# RedBoard.net
KiCad netlist of a schematic drawn in Altium Designer
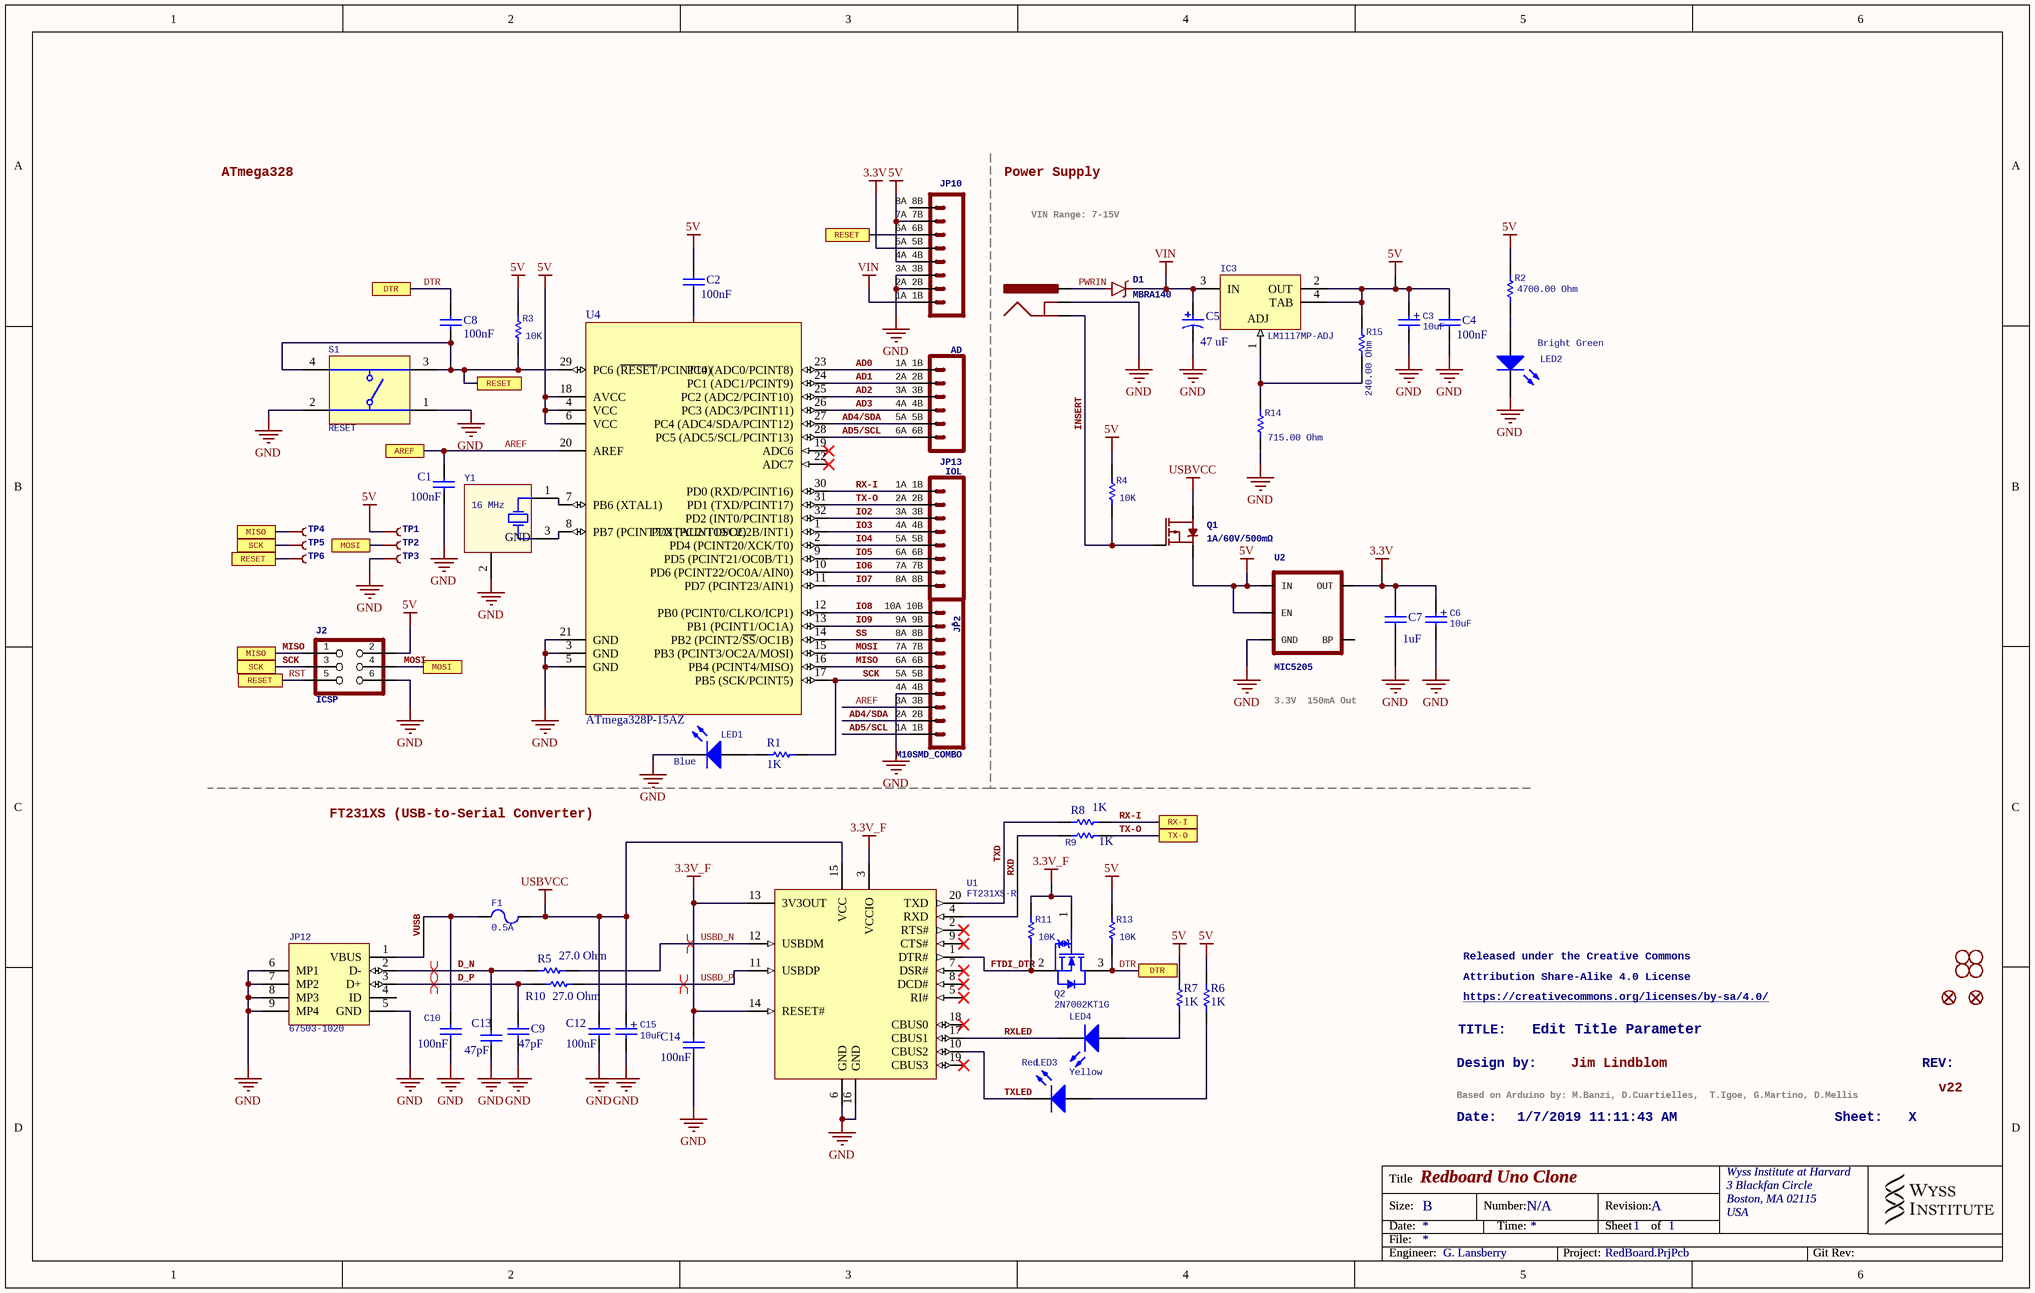
[diagram p0: RedBoard.SchDoc]

(export (version "E")
  (design (tool "Eeschema 10.0.6"))
  (components
    (comp (ref "C1")
      (value "100nF")
      (footprint "CAPC0402(1005)60_M")
      (description "CAP 100nF 10V -20% to +80% 0402 (1005 Metric) Thickness 0.6mm SMD")
      (fields (field (name "TOLERANCE") "-20% to +80%") (field (name "Comment") "CAP 100nF 10V 0402(1005)"))
      (libsource (lib "Altium Content Vault") (part "CAP"))
    )
    (comp (ref "C2")
      (value "100nF")
      (footprint "CAPC0402(1005)60_M")
      (description "CAP 100nF 10V -20% to +80% 0402 (1005 Metric) Thickness 0.6mm SMD")
      (fields (field (name "TOLERANCE") "-20% to +80%") (field (name "Comment") "CAP 100nF 10V 0402(1005)"))
      (libsource (lib "Altium Content Vault") (part "CAP"))
    )
    (comp (ref "C3")
      (value "10uF")
      (footprint "CAP_0603_TANT:CAPC2113X120X50NL20T30X")
      (fields
        (field (name "MANUFACTURER") "AVX Interconnect / Elco")
        (field (name "PART NUMBER") "TAJP106M010RNJ")
      )
      (libsource (lib "CAP_0603_TANT") (part "CAP_0603_TANT"))
    )
    (comp (ref "C4")
      (value "100nF")
      (footprint "CAPC0402(1005)60_M")
      (description "CAP 100nF 10V -20% to +80% 0402 (1005 Metric) Thickness 0.6mm SMD")
      (fields (field (name "TOLERANCE") "-20% to +80%") (field (name "Comment") "CAP 100nF 10V 0402(1005)"))
      (libsource (lib "Altium Content Vault") (part "CAP"))
    )
    (comp (ref "C5")
      (value "EEE-FT1E470AR")
      (footprint "PNSC-FT-V-53x53-2_V")
      (fields (field (name "CAP.") "47 uF") (field (name "MANUFACTURER") "Panasonic"))
      (libsource (lib "Altium Content Vault") (part "PNSC-CAP-P-2"))
    )
    (comp (ref "C6")
      (value "10uF")
      (footprint "CAP_0603_TANT:CAPC2113X120X50NL20T30X")
      (fields
        (field (name "MANUFACTURER") "AVX Interconnect / Elco")
        (field (name "PART NUMBER") "TAJP106M010RNJ")
      )
      (libsource (lib "CAP_0603_TANT") (part "CAP_0603_TANT"))
    )
    (comp (ref "C7")
      (value "1uF")
      (footprint "CAPC0402(1005)60_N")
      (description "CAP 1uF 10V -20% to +80% 0402 (1005 Metric) Thickness 0.6mm SMD")
      (fields (field (name "TOLERANCE") "-20% to +80%") (field (name "Comment") "CAP 1uF 10V 0402(1005)"))
      (libsource (lib "Altium Content Vault") (part "CAP"))
    )
    (comp (ref "C8")
      (value "100nF")
      (footprint "CAPC0402(1005)60_M")
      (description "CAP 100nF 10V -20% to +80% 0402 (1005 Metric) Thickness 0.6mm SMD")
      (fields (field (name "TOLERANCE") "-20% to +80%") (field (name "Comment") "CAP 100nF 10V 0402(1005)"))
      (libsource (lib "Altium Content Vault") (part "CAP"))
    )
    (comp (ref "C9")
      (value "47pF")
      (footprint "CAPC0402(1005)60_M")
      (description "CAP 47pF 10V ±1% 0402 (1005 Metric) Thickness 0.6mm SMD")
      (fields (field (name "TOLERANCE") "Â±1%") (field (name "Comment") "CAP 47pF 10V 0402(1005)"))
      (libsource (lib "Altium Content Vault") (part "CAP"))
    )
    (comp (ref "C10")
      (value "100nF")
      (footprint "CAPC0402(1005)60_M")
      (description "CAP 100nF 10V -20% to +80% 0402 (1005 Metric) Thickness 0.6mm SMD")
      (fields (field (name "TOLERANCE") "-20% to +80%") (field (name "Comment") "CAP 100nF 10V 0402(1005)"))
      (libsource (lib "Altium Content Vault") (part "CAP"))
    )
    (comp (ref "C12")
      (value "100nF")
      (footprint "CAPC0402(1005)60_M")
      (description "CAP 100nF 10V -20% to +80% 0402 (1005 Metric) Thickness 0.6mm SMD")
      (fields (field (name "TOLERANCE") "-20% to +80%") (field (name "Comment") "CAP 100nF 10V 0402(1005)"))
      (libsource (lib "Altium Content Vault") (part "CAP"))
    )
    (comp (ref "C13")
      (value "47pF")
      (footprint "CAPC0402(1005)60_M")
      (description "CAP 47pF 10V ±1% 0402 (1005 Metric) Thickness 0.6mm SMD")
      (fields (field (name "TOLERANCE") "Â±1%") (field (name "Comment") "CAP 47pF 10V 0402(1005)"))
      (libsource (lib "Altium Content Vault") (part "CAP"))
    )
    (comp (ref "C14")
      (value "100nF")
      (footprint "CAPC0402(1005)60_M")
      (description "CAP 100nF 10V -20% to +80% 0402 (1005 Metric) Thickness 0.6mm SMD")
      (fields (field (name "TOLERANCE") "-20% to +80%") (field (name "Comment") "CAP 100nF 10V 0402(1005)"))
      (libsource (lib "Altium Content Vault") (part "CAP"))
    )
    (comp (ref "C15")
      (value "10uF")
      (footprint "CAP_0603_TANT:CAPC2113X120X50NL20T30X")
      (fields
        (field (name "MANUFACTURER") "AVX Interconnect / Elco")
        (field (name "PART NUMBER") "TAJP106M010RNJ")
      )
      (libsource (lib "CAP_0603_TANT") (part "CAP_0603_TANT"))
    )
    (comp (ref "D1")
      (value "MBRA140")
      (footprint "ONSC-SMA-2-403D-02_V")
      (description "40V, 1A Schottky rectifierSMA/DO-214AC packageDIO-08053")
      (fields
        (field (name "MANUFACTURER") "ON Semiconductor")
        (field (name "MANUFACTURER PART NUMBER") "MBRA140T3G")
      )
      (libsource (lib "SparkFun-DiscreteSemi") (part "MBRA140"))
    )
    (comp (ref "F1")
      (value "0.5A")
      (footprint "LFUS-1812L050_V")
      (fields (field (name "TOLERANCE") "1%"))
      (libsource (lib "Altium Content Vault") (part "FUSE-2"))
    )
    (comp (ref "IC3")
      (value "LM1117MP-ADJ")
      (footprint "DCY0004A_L")
      (description "800mA Low-Dropout Linear Regulator, 4-pin SOT-223, Pb-Free")
      (fields
        (field (name "PARTNUMBER") "LM1117MP-ADJ/NOPB")
        (field (name "MANUFACTURER") "Texas Instruments")
      )
      (libsource (lib "Altium Content Vault") (part "PM-REG-LM1086ADJ-SOT4"))
    )
    (comp (ref "J2")
      (value "ICSP")
      (footprint "2X3_SMT_POSTS")
      (libsource (lib "SparkFun-Connectors") (part "AVR_SPI_PROG_3X2SMD"))
    )
    (comp (ref "J3")
      (value "POWER_JACKSUPER_BOMB_DIGITY")
      (footprint "POWER_JACK_SMD_OVERPASTE_SUPER_BOMB_DIGITY")
      (fields (field (name "LIBRARYNAME") "Testing"))
      (libsource (lib "Testing") (part "POWER_JACKSUPER_BOMB_DIGITY"))
    )
    (comp (ref "JP2")
      (value "M10SMD_COMBO")
      (footprint "1X10_SMD_COMBINED")
      (fields (field (name "NAME") "*"))
      (libsource (lib "SparkFun-Connectors") (part "M10SMD_COMBO"))
    )
    (comp (ref "JP3")
      (value "STAND-OFF")
      (footprint "STAND-OFF")
      (libsource (lib "SparkFun") (part "STAND-OFF"))
    )
    (comp (ref "JP4")
      (value "STAND-OFF")
      (footprint "STAND-OFF")
      (libsource (lib "SparkFun") (part "STAND-OFF"))
    )
    (comp (ref "JP5")
      (value "STAND-OFF")
      (footprint "STAND-OFF")
      (libsource (lib "SparkFun") (part "STAND-OFF"))
    )
    (comp (ref "JP6")
      (value "STAND-OFF")
      (footprint "STAND-OFF")
      (libsource (lib "SparkFun") (part "STAND-OFF"))
    )
    (comp (ref "JP8")
      (value "FIDUCIAL1X2")
      (footprint "FID")
      (description "Fiducial Alignment PointsVarious fiducial points for machine vision alignment.")
      (libsource (lib "SparkFun") (part "FIDUCIAL1X2"))
    )
    (comp (ref "JP9")
      (value "FIDUCIAL1X2")
      (footprint "FID")
      (description "Fiducial Alignment PointsVarious fiducial points for machine vision alignment.")
      (libsource (lib "SparkFun") (part "FIDUCIAL1X2"))
    )
    (comp (ref "JP10")
      (value "M08SMD-COMBO")
      (footprint "1X08_SMD_COMBINED")
      (libsource (lib "SparkFun-Connectors") (part "M08SMD-COMBO"))
    )
    (comp (ref "JP11")
      (value "IOL")
      (footprint "1X08_SMD_COMBINED")
      (libsource (lib "SparkFun-Connectors") (part "M08SMD-COMBO"))
    )
    (comp (ref "JP12")
      (value "67503-1020")
      (footprint "MOLX-67503-1020_V")
      (description "USB, MINI, SMD, RA KME04-USBMU03A01")
      (fields (field (name "MANUFACTURER") "Molex"))
      (libsource (lib "Altium Content Vault") (part "MOLX-67503-1020"))
    )
    (comp (ref "JP13")
      (value "AD")
      (footprint "1X06_SMD_STRAIGHT_COMBO")
      (libsource (lib "SparkFun-Connectors") (part "M06SMD-STRAIGHT-COMBO"))
    )
    (comp (ref "LED1")
      (value "150060BS75000")
      (footprint "0603_A")
      (description "SMD mono-color Chip LED, WL-SMCW, Blue")
      (fields (field (name "COLOR") "Blue") (field (name "MANUFACTURER") "Wuerth Elektronik"))
      (libsource (lib "Altium Content Vault") (part "WE-LED_K1A2-2"))
    )
    (comp (ref "LED2")
      (value "150060VS75000")
      (footprint "0603_A")
      (description "SMD mono-color Chip LED, WL-SMCW, Bright Green")
      (fields (field (name "COLOR") "Bright Green") (field (name "MANUFACTURER") "Wuerth Elektronik"))
      (libsource (lib "Altium Content Vault") (part "WE-LED_K1A2-2"))
    )
    (comp (ref "LED3")
      (value "150060RS75000")
      (footprint "0603_A")
      (description "SMD mono-color Chip LED, WL-SMCW, Red")
      (fields (field (name "COLOR") "Red") (field (name "MANUFACTURER") "Wuerth Elektronik"))
      (libsource (lib "Altium Content Vault") (part "WE-LED_K1A2-2"))
    )
    (comp (ref "LED4")
      (value "150060YS75000")
      (footprint "0603_A")
      (description "SMD mono-color Chip LED, WL-SMCW, Yellow")
      (fields (field (name "COLOR") "Yellow") (field (name "MANUFACTURER") "Wuerth Elektronik"))
      (libsource (lib "Altium Content Vault") (part "WE-LED_K1A2-2"))
    )
    (comp (ref "Q1")
      (value "1A/60V/500mΩ")
      (footprint "SOT23-3")
      (description "P-channel MOSFETsVoltage controlled devices that allow control of high current outputs.")
      (fields
        (field (name "MANUFACTURER") "Diodes Zetex")
        (field (name "MANUFACTURER PART NUMBER") "ZXMP6A13FTA")
      )
      (libsource (lib "SparkFun-DiscreteSemi") (part "MOSFET-PCH-ZXMP6A13F"))
    )
    (comp (ref "Q2")
      (value "2N7002KT1G")
      (footprint "ONSC-SOT-23-3-318-08_V")
      (description "Small Signal MOSFET, 60 V, 380 mA, Single, N-Channel, 3-Pin SOT-23, Pb-Free, Tape and Reel")
      (fields (field (name "MANUFACTURER") "On Semiconductor"))
      (libsource (lib "Altium Content Vault") (part "ONSC-NMOS-G1S2D3-3_B"))
    )
    (comp (ref "R1")
      (value "1K")
      (footprint "RESC0402(1005)_L")
      (description "1K 0.063W 1% 0402 (1005 Metric)  SMD")
      (fields (field (name "TOLERANCE") "1 %") (field (name "POWER") "0.063 W"))
      (libsource (lib "Altium Content Vault") (part "RES"))
    )
    (comp (ref "R2")
      (value "4700.00 Ohm")
      (footprint "RESC0402(1005)_N")
      (description "4K7 0.063W 1% 0402 (1005 Metric)  SMD")
      (fields (field (name "POWER") "0.063 W") (field (name "TOLERANCE") "1 %"))
      (libsource (lib "Altium Content Vault") (part "RES"))
    )
    (comp (ref "R3")
      (value "10K")
      (footprint "RESC0402(1005)_N")
      (description "10K 0.063W 1% 0402 (1005 Metric)  SMD")
      (fields (field (name "TOLERANCE") "1 %") (field (name "POWER") "0.063 W"))
      (libsource (lib "Altium Content Vault") (part "RES"))
    )
    (comp (ref "R4")
      (value "10K")
      (footprint "RESC0402(1005)_N")
      (description "10K 0.063W 1% 0402 (1005 Metric)  SMD")
      (fields (field (name "TOLERANCE") "1 %") (field (name "POWER") "0.063 W"))
      (libsource (lib "Altium Content Vault") (part "RES"))
    )
    (comp (ref "R5")
      (value "27.0 Ohm")
      (footprint "RESC0402(1005)_M")
      (description "27R 0.063W 1% 0402 (1005 Metric)  SMD")
      (fields (field (name "POWER") "0.063 W") (field (name "TOLERANCE") "1 %"))
      (libsource (lib "Altium Content Vault") (part "RES"))
    )
    (comp (ref "R6")
      (value "1K")
      (footprint "RESC0402(1005)_L")
      (description "1K 0.063W 1% 0402 (1005 Metric)  SMD")
      (fields (field (name "TOLERANCE") "1 %") (field (name "POWER") "0.063 W"))
      (libsource (lib "Altium Content Vault") (part "RES"))
    )
    (comp (ref "R7")
      (value "1K")
      (footprint "RESC0402(1005)_L")
      (description "1K 0.063W 1% 0402 (1005 Metric)  SMD")
      (fields (field (name "TOLERANCE") "1 %") (field (name "POWER") "0.063 W"))
      (libsource (lib "Altium Content Vault") (part "RES"))
    )
    (comp (ref "R8")
      (value "1K")
      (footprint "RESC0402(1005)_L")
      (description "1K 0.063W 1% 0402 (1005 Metric)  SMD")
      (fields (field (name "TOLERANCE") "1 %") (field (name "POWER") "0.063 W"))
      (libsource (lib "Altium Content Vault") (part "RES"))
    )
    (comp (ref "R9")
      (value "1K")
      (footprint "RESC0402(1005)_L")
      (description "1K 0.063W 1% 0402 (1005 Metric)  SMD")
      (fields (field (name "TOLERANCE") "1 %") (field (name "POWER") "0.063 W"))
      (libsource (lib "Altium Content Vault") (part "RES"))
    )
    (comp (ref "R10")
      (value "27.0 Ohm")
      (footprint "RESC0402(1005)_M")
      (description "27R 0.063W 1% 0402 (1005 Metric)  SMD")
      (fields (field (name "POWER") "0.063 W") (field (name "TOLERANCE") "1 %"))
      (libsource (lib "Altium Content Vault") (part "RES"))
    )
    (comp (ref "R11")
      (value "10K")
      (footprint "RESC0402(1005)_N")
      (description "10K 0.063W 1% 0402 (1005 Metric)  SMD")
      (fields (field (name "TOLERANCE") "1 %") (field (name "POWER") "0.063 W"))
      (libsource (lib "Altium Content Vault") (part "RES"))
    )
    (comp (ref "R13")
      (value "10K")
      (footprint "RESC0402(1005)_N")
      (description "10K 0.063W 1% 0402 (1005 Metric)  SMD")
      (fields (field (name "TOLERANCE") "1 %") (field (name "POWER") "0.063 W"))
      (libsource (lib "Altium Content Vault") (part "RES"))
    )
    (comp (ref "R14")
      (value "715.00 Ohm")
      (footprint "RESC0402(1005)_M")
      (description "715R 0.063W 1% 0402 (1005 Metric)  SMD")
      (fields (field (name "POWER") "0.063 W") (field (name "TOLERANCE") "1 %"))
      (libsource (lib "Altium Content Vault") (part "RES"))
    )
    (comp (ref "R15")
      (value "240.00 Ohm")
      (footprint "RESC0402(1005)_L")
      (description "240R 0.063W 1% 0402 (1005 Metric)  SMD")
      (fields (field (name "POWER") "0.063 W") (field (name "TOLERANCE") "1 %"))
      (libsource (lib "Altium Content Vault") (part "RES"))
    )
    (comp (ref "S1")
      (value "RESET")
      (footprint "TECO-FSM4JSMATR_V")
      (description "Micro Miniature Push Button Switch FSM JSM, 50 mA, -35 to 85 degC, 4-Pin SMD, RoHS, Tape and Reel")
      (fields (field (name "MANUFACTURER") "TE Connectivity"))
      (libsource (lib "Altium Content Vault") (part "SW-SPST-4_A"))
    )
    (comp (ref "TP1")
      (value "TP-3x5")
      (footprint "PAD.03X.05")
      (description "Bare copper test points for troubleshooting or ICT")
      (libsource (lib "SparkFun-Connectors") (part "TEST-POINT3X5"))
    )
    (comp (ref "TP2")
      (value "TP-3x5")
      (footprint "PAD.03X.05")
      (description "Bare copper test points for troubleshooting or ICT")
      (libsource (lib "SparkFun-Connectors") (part "TEST-POINT3X5"))
    )
    (comp (ref "TP3")
      (value "TP-3x5")
      (footprint "PAD.03X.05")
      (description "Bare copper test points for troubleshooting or ICT")
      (libsource (lib "SparkFun-Connectors") (part "TEST-POINT3X5"))
    )
    (comp (ref "TP4")
      (value "TP-3x5")
      (footprint "PAD.03X.05")
      (description "Bare copper test points for troubleshooting or ICT")
      (libsource (lib "SparkFun-Connectors") (part "TEST-POINT3X5"))
    )
    (comp (ref "TP5")
      (value "TP-3x5")
      (footprint "PAD.03X.05")
      (description "Bare copper test points for troubleshooting or ICT")
      (libsource (lib "SparkFun-Passives") (part "TEST-POINT3X5"))
    )
    (comp (ref "TP6")
      (value "TP-3x5")
      (footprint "PAD.03X.05")
      (description "Bare copper test points for troubleshooting or ICT")
      (libsource (lib "SparkFun-Connectors") (part "TEST-POINT3X5"))
    )
    (comp (ref "U1")
      (value "FT231XS-R")
      (footprint "SSOP-20_L")
      (fields (field (name "MANUFACTURER") "FTDI"))
      (libsource (lib "Altium Content Vault") (part "COM-USB-FT231XS-IL20"))
    )
    (comp (ref "U2")
      (value "MIC5205")
      (footprint "SOT-23-5:SOT-23-5")
      (description "MIC5205 150mA vreg3.3V - VREG-008225V - VREG-00823")
      (fields
        (field (name "MANUFACTURER") "Microchip Micrel")
        (field (name "MANUFACTURER PART NUMBER") "MIC5205-3.3YM5-TR")
      )
      (libsource (lib "SparkFun-PowerIC") (part "MIC52053.3V"))
    )
    (comp (ref "U4")
      (value "ATmega328P-15AZ")
      (footprint "32MA_M")
      (fields
        (field (name "MANUFACTURER") "Microchip / Atmel")
        (field (name "MANUFACTURER PART NUMBER") "ATMEGA328P-AUR")
      )
      (libsource (lib "Altium Content Vault") (part "MC-8B-ATM48-SQ32"))
    )
    (comp (ref "Y1")
      (value "CSTCE16M0V53-R0")
      (footprint "MURA-CSTCE_V-3_V")
      (fields
        (field (name "OSCILLATING FREQUENCY") "16 MHz")
        (field (name "MANUFACTURER") "Murata")
        (field (name "MANUFACTURER PART NUMBER") "CSTNE16M0V530000R0")
      )
      (libsource (lib "Altium Content Vault") (part "MURA-CSTCE_V-3"))
    )
  )
  (nets
    (net (code "1") (name "/AD0") (class "Default")
      (node (ref "JP13") (pin "1A_1B") (pinfunction "1_1A_1B") (pintype "passive"))
      (node (ref "U4") (pin "23") (pinfunction "PC0_(ADC0/PCINT8)_23") (pintype "bidirectional"))
    )
    (net (code "2") (name "/AD1") (class "Default")
      (node (ref "JP13") (pin "2A_2B") (pinfunction "2_2A_2B") (pintype "passive"))
      (node (ref "U4") (pin "24") (pinfunction "PC1_(ADC1/PCINT9)_24") (pintype "bidirectional"))
    )
    (net (code "3") (name "/AD2") (class "Default")
      (node (ref "JP13") (pin "3A_3B") (pinfunction "3_3A_3B") (pintype "passive"))
      (node (ref "U4") (pin "25") (pinfunction "PC2_(ADC2/PCINT10)_25") (pintype "bidirectional"))
    )
    (net (code "4") (name "/AD3") (class "Default")
      (node (ref "JP13") (pin "4A_4B") (pinfunction "4_4A_4B") (pintype "passive"))
      (node (ref "U4") (pin "26") (pinfunction "PC3_(ADC3/PCINT11)_26") (pintype "bidirectional"))
    )
    (net (code "5") (name "/AD4{slash}SDA") (class "Default")
      (node (ref "JP13") (pin "5A_5B") (pinfunction "5_5A_5B") (pintype "passive"))
      (node (ref "JP2") (pin "2A_2B") (pinfunction "2_2A_2B") (pintype "passive"))
      (node (ref "U4") (pin "27") (pinfunction "PC4_(ADC4/SDA/PCINT12)_27") (pintype "bidirectional"))
    )
    (net (code "6") (name "/AD5{slash}SCL") (class "Default")
      (node (ref "JP13") (pin "6A_6B") (pinfunction "6_6A_6B") (pintype "passive"))
      (node (ref "JP2") (pin "1A_1B") (pinfunction "1_1A_1B") (pintype "passive"))
      (node (ref "U4") (pin "28") (pinfunction "PC5_(ADC5/SCL/PCINT13)_28") (pintype "bidirectional"))
    )
    (net (code "7") (name "/AREF") (class "Default")
      (node (ref "C1") (pin "2") (pinfunction "2_2") (pintype "passive"))
      (node (ref "JP2") (pin "3A_3B") (pinfunction "3_3A_3B") (pintype "passive"))
      (node (ref "U4") (pin "20") (pinfunction "AREF_20") (pintype "passive"))
    )
    (net (code "8") (name "/DTR") (class "Default")
      (node (ref "C8") (pin "1") (pinfunction "1_1") (pintype "passive"))
      (node (ref "Q2") (pin "3") (pinfunction "D_3") (pintype "passive"))
      (node (ref "R13") (pin "1") (pinfunction "1_1") (pintype "passive"))
    )
    (net (code "9") (name "/D_N") (class "Default")
      (node (ref "C13") (pin "2") (pinfunction "2_2") (pintype "passive"))
      (node (ref "JP12") (pin "2") (pinfunction "D-_2") (pintype "bidirectional"))
      (node (ref "R5") (pin "1") (pinfunction "1_1") (pintype "passive"))
    )
    (net (code "10") (name "/D_P") (class "Default")
      (node (ref "C9") (pin "2") (pinfunction "2_2") (pintype "passive"))
      (node (ref "JP12") (pin "3") (pinfunction "D+_3") (pintype "bidirectional"))
      (node (ref "R10") (pin "1") (pinfunction "1_1") (pintype "passive"))
    )
    (net (code "11") (name "/FTDI_DTR") (class "Default")
      (node (ref "Q2") (pin "2") (pinfunction "S_2") (pintype "passive"))
      (node (ref "R11") (pin "1") (pinfunction "1_1") (pintype "passive"))
      (node (ref "U1") (pin "1") (pinfunction "DTR#_1") (pintype "output"))
    )
    (net (code "12") (name "/INSERT") (class "Default")
      (node (ref "J3") (pin "P$4") (pinfunction "GND_P$4") (pintype "passive"))
      (node (ref "Q1") (pin "1") (pinfunction "G_1") (pintype "passive"))
      (node (ref "R4") (pin "1") (pinfunction "1_1") (pintype "passive"))
    )
    (net (code "13") (name "/IO2") (class "Default")
      (node (ref "JP11") (pin "3A_3B") (pinfunction "3_3A_3B") (pintype "passive"))
      (node (ref "U4") (pin "32") (pinfunction "PD2_(INT0/PCINT18)_32") (pintype "bidirectional"))
    )
    (net (code "14") (name "/IO3") (class "Default")
      (node (ref "JP11") (pin "4A_4B") (pinfunction "4_4A_4B") (pintype "passive"))
      (node (ref "U4") (pin "1") (pinfunction "PD3_(PCINT19/OC2B/INT1)_1") (pintype "bidirectional"))
    )
    (net (code "15") (name "/IO4") (class "Default")
      (node (ref "JP11") (pin "5A_5B") (pinfunction "5_5A_5B") (pintype "passive"))
      (node (ref "U4") (pin "2") (pinfunction "PD4_(PCINT20/XCK/T0)_2") (pintype "bidirectional"))
    )
    (net (code "16") (name "/IO5") (class "Default")
      (node (ref "JP11") (pin "6A_6B") (pinfunction "6_6A_6B") (pintype "passive"))
      (node (ref "U4") (pin "9") (pinfunction "PD5_(PCINT21/OC0B/T1)_9") (pintype "bidirectional"))
    )
    (net (code "17") (name "/IO6") (class "Default")
      (node (ref "JP11") (pin "7A_7B") (pinfunction "7_7A_7B") (pintype "passive"))
      (node (ref "U4") (pin "10") (pinfunction "PD6_(PCINT22/OC0A/AIN0)_10") (pintype "bidirectional"))
    )
    (net (code "18") (name "/IO7") (class "Default")
      (node (ref "JP11") (pin "8A_8B") (pinfunction "8_8A_8B") (pintype "passive"))
      (node (ref "U4") (pin "11") (pinfunction "PD7_(PCINT23/AIN1)_11") (pintype "bidirectional"))
    )
    (net (code "19") (name "/IO8") (class "Default")
      (node (ref "JP2") (pin "10A_10B") (pinfunction "10_10A_10B") (pintype "passive"))
      (node (ref "U4") (pin "12") (pinfunction "PB0_(PCINT0/CLKO/ICP1)_12") (pintype "bidirectional"))
    )
    (net (code "20") (name "/IO9") (class "Default")
      (node (ref "JP2") (pin "9A_9B") (pinfunction "9_9A_9B") (pintype "passive"))
      (node (ref "U4") (pin "13") (pinfunction "PB1_(PCINT1/OC1A)_13") (pintype "bidirectional"))
    )
    (net (code "21") (name "/MISO") (class "Default")
      (node (ref "J2") (pin "1") (pinfunction "1_1") (pintype "passive"))
      (node (ref "JP2") (pin "6A_6B") (pinfunction "6_6A_6B") (pintype "passive"))
      (node (ref "TP4") (pin "P$1") (pinfunction "1_P$1") (pintype "passive"))
      (node (ref "U4") (pin "16") (pinfunction "PB4_(PCINT4/MISO)_16") (pintype "bidirectional"))
    )
    (net (code "22") (name "/MOSI") (class "Default")
      (node (ref "J2") (pin "4") (pinfunction "4_4") (pintype "passive"))
      (node (ref "JP2") (pin "7A_7B") (pinfunction "7_7A_7B") (pintype "passive"))
      (node (ref "TP2") (pin "P$1") (pinfunction "1_P$1") (pintype "passive"))
      (node (ref "U4") (pin "15") (pinfunction "PB3_(PCINT3/OC2A/MOSI)_15") (pintype "bidirectional"))
    )
    (net (code "23") (name "/PWRIN") (class "Default")
      (node (ref "D1") (pin "A") (pinfunction "A_A") (pintype "passive"))
      (node (ref "J3") (pin "VIN0") (pinfunction "PWR_VIN0") (pintype "passive"))
    )
    (net (code "24") (name "/RST") (class "Default")
      (node (ref "C8") (pin "2") (pinfunction "2_2") (pintype "passive"))
      (node (ref "J2") (pin "5") (pinfunction "5_5") (pintype "passive"))
      (node (ref "JP10") (pin "6A_6B") (pinfunction "6_6A_6B") (pintype "passive"))
      (node (ref "R3") (pin "1") (pinfunction "1_1") (pintype "passive"))
      (node (ref "S1") (pin "3") (pinfunction "3_3") (pintype "passive"))
      (node (ref "S1") (pin "4") (pinfunction "4_4") (pintype "passive"))
      (node (ref "TP6") (pin "P$1") (pinfunction "1_P$1") (pintype "passive"))
      (node (ref "U4") (pin "29") (pinfunction "PC6_(~{RESET}/PCINT14)_29") (pintype "bidirectional"))
    )
    (net (code "25") (name "/RX-I") (class "Default")
      (node (ref "JP11") (pin "1A_1B") (pinfunction "1_1A_1B") (pintype "passive"))
      (node (ref "R8") (pin "1") (pinfunction "1_1") (pintype "passive"))
      (node (ref "U4") (pin "30") (pinfunction "PD0_(RXD/PCINT16)_30") (pintype "bidirectional"))
    )
    (net (code "26") (name "/RXD") (class "Default")
      (node (ref "R9") (pin "2") (pinfunction "2_2") (pintype "passive"))
      (node (ref "U1") (pin "4") (pinfunction "RXD_4") (pintype "input"))
    )
    (net (code "27") (name "/RXLED") (class "Default")
      (node (ref "LED4") (pin "1") (pinfunction "K_1") (pintype "passive"))
      (node (ref "U1") (pin "17") (pinfunction "CBUS1_17") (pintype "bidirectional"))
    )
    (net (code "28") (name "/SCK") (class "Default")
      (node (ref "J2") (pin "3") (pinfunction "3_3") (pintype "passive"))
      (node (ref "JP2") (pin "5A_5B") (pinfunction "5_5A_5B") (pintype "passive"))
      (node (ref "R1") (pin "1") (pinfunction "1_1") (pintype "passive"))
      (node (ref "TP5") (pin "P$1") (pinfunction "1_P$1") (pintype "passive"))
      (node (ref "U4") (pin "17") (pinfunction "PB5_(SCK/PCINT5)_17") (pintype "bidirectional"))
    )
    (net (code "29") (name "/SS") (class "Default")
      (node (ref "JP2") (pin "8A_8B") (pinfunction "8_8A_8B") (pintype "passive"))
      (node (ref "U4") (pin "14") (pinfunction "PB2_(PCINT2/~{SS}/OC1B)_14") (pintype "bidirectional"))
    )
    (net (code "30") (name "/TX-O") (class "Default")
      (node (ref "JP11") (pin "2A_2B") (pinfunction "2_2A_2B") (pintype "passive"))
      (node (ref "R9") (pin "1") (pinfunction "1_1") (pintype "passive"))
      (node (ref "U4") (pin "31") (pinfunction "PD1_(TXD/PCINT17)_31") (pintype "bidirectional"))
    )
    (net (code "31") (name "/TXD") (class "Default")
      (node (ref "R8") (pin "2") (pinfunction "2_2") (pintype "passive"))
      (node (ref "U1") (pin "20") (pinfunction "TXD_20") (pintype "output"))
    )
    (net (code "32") (name "/TXLED") (class "Default")
      (node (ref "LED3") (pin "1") (pinfunction "K_1") (pintype "passive"))
      (node (ref "U1") (pin "10") (pinfunction "CBUS2_10") (pintype "bidirectional"))
    )
    (net (code "33") (name "/USBD_N") (class "Default")
      (node (ref "R5") (pin "2") (pinfunction "2_2") (pintype "passive"))
      (node (ref "U1") (pin "12") (pinfunction "USBDM_12") (pintype "input"))
    )
    (net (code "34") (name "/USBD_P") (class "Default")
      (node (ref "R10") (pin "2") (pinfunction "2_2") (pintype "passive"))
      (node (ref "U1") (pin "11") (pinfunction "USBDP_11") (pintype "input"))
    )
    (net (code "35") (name "/VUSB") (class "Default")
      (node (ref "C10") (pin "2") (pinfunction "2_2") (pintype "passive"))
      (node (ref "F1") (pin "1") (pinfunction "1_1") (pintype "passive"))
      (node (ref "JP12") (pin "1") (pinfunction "VBUS_1") (pintype "power_in"))
    )
    (net (code "36") (name "3.3V") (class "Default")
      (node (ref "C6") (pin "1") (pinfunction "1_1") (pintype "passive"))
      (node (ref "C7") (pin "2") (pinfunction "2_2") (pintype "passive"))
      (node (ref "JP10") (pin "5A_5B") (pinfunction "5_5A_5B") (pintype "passive"))
      (node (ref "U2") (pin "5") (pinfunction "OUT_5") (pintype "passive"))
    )
    (net (code "37") (name "3.3V_F") (class "Default")
      (node (ref "C14") (pin "2") (pinfunction "2_2") (pintype "passive"))
      (node (ref "Q2") (pin "1") (pinfunction "G_1") (pintype "passive"))
      (node (ref "R11") (pin "2") (pinfunction "2_2") (pintype "passive"))
      (node (ref "U1") (pin "13") (pinfunction "3V3OUT_13") (pintype "power_in"))
      (node (ref "U1") (pin "14") (pinfunction "RESET#_14") (pintype "input"))
      (node (ref "U1") (pin "3") (pinfunction "VCCIO_3") (pintype "power_in"))
    )
    (net (code "38") (name "5V") (class "Default")
      (node (ref "C2") (pin "2") (pinfunction "2_2") (pintype "passive"))
      (node (ref "C3") (pin "1") (pinfunction "1_1") (pintype "passive"))
      (node (ref "C4") (pin "2") (pinfunction "2_2") (pintype "passive"))
      (node (ref "IC3") (pin "2") (pinfunction "OUT_2") (pintype "power_in"))
      (node (ref "IC3") (pin "4") (pinfunction "TAB_4") (pintype "power_in"))
      (node (ref "J2") (pin "2") (pinfunction "2_2") (pintype "passive"))
      (node (ref "JP10") (pin "4A_4B") (pinfunction "4_4A_4B") (pintype "passive"))
      (node (ref "JP10") (pin "7A_7B") (pinfunction "7_7A_7B") (pintype "passive"))
      (node (ref "Q1") (pin "2") (pinfunction "S_2") (pintype "passive"))
      (node (ref "R13") (pin "2") (pinfunction "2_2") (pintype "passive"))
      (node (ref "R15") (pin "2") (pinfunction "2_2") (pintype "passive"))
      (node (ref "R2") (pin "2") (pinfunction "2_2") (pintype "passive"))
      (node (ref "R3") (pin "2") (pinfunction "2_2") (pintype "passive"))
      (node (ref "R4") (pin "2") (pinfunction "2_2") (pintype "passive"))
      (node (ref "R6") (pin "1") (pinfunction "1_1") (pintype "passive"))
      (node (ref "R7") (pin "1") (pinfunction "1_1") (pintype "passive"))
      (node (ref "TP1") (pin "P$1") (pinfunction "1_P$1") (pintype "passive"))
      (node (ref "U2") (pin "1") (pinfunction "IN_1") (pintype "passive"))
      (node (ref "U2") (pin "3") (pinfunction "EN_3") (pintype "passive"))
      (node (ref "U4") (pin "18") (pinfunction "AVCC_18") (pintype "power_in"))
      (node (ref "U4") (pin "4") (pinfunction "VCC_4") (pintype "power_in"))
      (node (ref "U4") (pin "6") (pinfunction "VCC_6") (pintype "power_in"))
    )
    (net (code "39") (name "GND") (class "Default")
      (node (ref "C1") (pin "1") (pinfunction "1_1") (pintype "passive"))
      (node (ref "C10") (pin "1") (pinfunction "1_1") (pintype "passive"))
      (node (ref "C12") (pin "1") (pinfunction "1_1") (pintype "passive"))
      (node (ref "C13") (pin "1") (pinfunction "1_1") (pintype "passive"))
      (node (ref "C14") (pin "1") (pinfunction "1_1") (pintype "passive"))
      (node (ref "C15") (pin "2") (pinfunction "2_2") (pintype "passive"))
      (node (ref "C2") (pin "1") (pinfunction "1_1") (pintype "passive"))
      (node (ref "C3") (pin "2") (pinfunction "2_2") (pintype "passive"))
      (node (ref "C4") (pin "1") (pinfunction "1_1") (pintype "passive"))
      (node (ref "C5") (pin "2") (pinfunction "2_2") (pintype "passive"))
      (node (ref "C6") (pin "2") (pinfunction "2_2") (pintype "passive"))
      (node (ref "C7") (pin "1") (pinfunction "1_1") (pintype "passive"))
      (node (ref "C9") (pin "1") (pinfunction "1_1") (pintype "passive"))
      (node (ref "J2") (pin "6") (pinfunction "6_6") (pintype "passive"))
      (node (ref "J3") (pin "GND") (pinfunction "GNDBREAK_GND") (pintype "passive"))
      (node (ref "JP10") (pin "2A_2B") (pinfunction "2_2A_2B") (pintype "passive"))
      (node (ref "JP10") (pin "3A_3B") (pinfunction "3_3A_3B") (pintype "passive"))
      (node (ref "JP12") (pin "5") (pinfunction "GND_5") (pintype "power_in"))
      (node (ref "JP12") (pin "6") (pinfunction "MP1_6") (pintype "passive"))
      (node (ref "JP12") (pin "7") (pinfunction "MP2_7") (pintype "passive"))
      (node (ref "JP12") (pin "8") (pinfunction "MP3_8") (pintype "passive"))
      (node (ref "JP12") (pin "9") (pinfunction "MP4_9") (pintype "passive"))
      (node (ref "JP2") (pin "4A_4B") (pinfunction "4_4A_4B") (pintype "passive"))
      (node (ref "LED1") (pin "1") (pinfunction "K_1") (pintype "passive"))
      (node (ref "LED2") (pin "1") (pinfunction "K_1") (pintype "passive"))
      (node (ref "R14") (pin "1") (pinfunction "1_1") (pintype "passive"))
      (node (ref "S1") (pin "1") (pinfunction "1_1") (pintype "passive"))
      (node (ref "S1") (pin "2") (pinfunction "2_2") (pintype "passive"))
      (node (ref "TP3") (pin "P$1") (pinfunction "1_P$1") (pintype "passive"))
      (node (ref "U1") (pin "16") (pinfunction "GND_16") (pintype "power_in"))
      (node (ref "U1") (pin "6") (pinfunction "GND_6") (pintype "power_in"))
      (node (ref "U2") (pin "2") (pinfunction "GND_2") (pintype "passive"))
      (node (ref "U4") (pin "21") (pinfunction "GND_21") (pintype "power_in"))
      (node (ref "U4") (pin "3") (pinfunction "GND_3") (pintype "power_in"))
      (node (ref "U4") (pin "5") (pinfunction "GND_5") (pintype "power_in"))
      (node (ref "Y1") (pin "2") (pinfunction "GND_2") (pintype "power_in"))
    )
    (net (code "40") (name "Net-(IC3-ADJ)") (class "Default")
      (node (ref "IC3") (pin "1") (pinfunction "ADJ_1") (pintype "input"))
      (node (ref "R14") (pin "2") (pinfunction "2_2") (pintype "passive"))
      (node (ref "R15") (pin "1") (pinfunction "1_1") (pintype "passive"))
    )
    (net (code "41") (name "Net-(LED1-A)") (class "Default")
      (node (ref "LED1") (pin "2") (pinfunction "A_2") (pintype "passive"))
      (node (ref "R1") (pin "2") (pinfunction "2_2") (pintype "passive"))
    )
    (net (code "42") (name "Net-(LED2-A)") (class "Default")
      (node (ref "LED2") (pin "2") (pinfunction "A_2") (pintype "passive"))
      (node (ref "R2") (pin "1") (pinfunction "1_1") (pintype "passive"))
    )
    (net (code "43") (name "Net-(LED3-A)") (class "Default")
      (node (ref "LED3") (pin "2") (pinfunction "A_2") (pintype "passive"))
      (node (ref "R6") (pin "2") (pinfunction "2_2") (pintype "passive"))
    )
    (net (code "44") (name "Net-(LED4-A)") (class "Default")
      (node (ref "LED4") (pin "2") (pinfunction "A_2") (pintype "passive"))
      (node (ref "R7") (pin "2") (pinfunction "2_2") (pintype "passive"))
    )
    (net (code "45") (name "Net-(U4-PB6_(XTAL1))") (class "Default")
      (node (ref "U4") (pin "7") (pinfunction "PB6_(XTAL1)_7") (pintype "bidirectional"))
      (node (ref "Y1") (pin "1") (pinfunction "C1_1") (pintype "passive"))
    )
    (net (code "46") (name "Net-(U4-PB7_(PCINT7{slash}XTAL2{slash}TOSC2))") (class "Default")
      (node (ref "U4") (pin "8") (pinfunction "PB7_(PCINT7/XTAL2/TOSC2)_8") (pintype "bidirectional"))
      (node (ref "Y1") (pin "3") (pinfunction "C2_3") (pintype "passive"))
    )
    (net (code "47") (name "USBVCC") (class "Default")
      (node (ref "C12") (pin "2") (pinfunction "2_2") (pintype "passive"))
      (node (ref "C15") (pin "1") (pinfunction "1_1") (pintype "passive"))
      (node (ref "F1") (pin "2") (pinfunction "2_2") (pintype "passive"))
      (node (ref "Q1") (pin "3") (pinfunction "D_3") (pintype "passive"))
      (node (ref "U1") (pin "15") (pinfunction "VCC_15") (pintype "power_in"))
    )
    (net (code "48") (name "VIN") (class "Default")
      (node (ref "C5") (pin "1") (pinfunction "1_1") (pintype "passive"))
      (node (ref "D1") (pin "C") (pinfunction "C_C") (pintype "passive"))
      (node (ref "IC3") (pin "3") (pinfunction "IN_3") (pintype "power_in"))
      (node (ref "JP10") (pin "1A_1B") (pinfunction "1_1A_1B") (pintype "passive"))
    )
    (net (code "49") (name "unconnected-(JP10-8-Pad8A_8B)") (class "Default")
      (node (ref "JP10") (pin "8A_8B") (pinfunction "8_8A_8B") (pintype "passive"))
    )
    (net (code "50") (name "unconnected-(JP12-ID-Pad4)") (class "Default")
      (node (ref "JP12") (pin "4") (pinfunction "ID_4") (pintype "passive"))
    )
    (net (code "51") (name "unconnected-(U1-CBUS0-Pad18)") (class "Default")
      (node (ref "U1") (pin "18") (pinfunction "CBUS0_18") (pintype "bidirectional+no_connect"))
    )
    (net (code "52") (name "unconnected-(U1-CBUS3-Pad19)") (class "Default")
      (node (ref "U1") (pin "19") (pinfunction "CBUS3_19") (pintype "bidirectional+no_connect"))
    )
    (net (code "53") (name "unconnected-(U1-CTS#-Pad9)") (class "Default")
      (node (ref "U1") (pin "9") (pinfunction "CTS#_9") (pintype "input+no_connect"))
    )
    (net (code "54") (name "unconnected-(U1-DCD#-Pad8)") (class "Default")
      (node (ref "U1") (pin "8") (pinfunction "DCD#_8") (pintype "input+no_connect"))
    )
    (net (code "55") (name "unconnected-(U1-DSR#-Pad7)") (class "Default")
      (node (ref "U1") (pin "7") (pinfunction "DSR#_7") (pintype "input+no_connect"))
    )
    (net (code "56") (name "unconnected-(U1-RI#-Pad5)") (class "Default")
      (node (ref "U1") (pin "5") (pinfunction "RI#_5") (pintype "input+no_connect"))
    )
    (net (code "57") (name "unconnected-(U1-RTS#-Pad2)") (class "Default")
      (node (ref "U1") (pin "2") (pinfunction "RTS#_2") (pintype "output+no_connect"))
    )
    (net (code "58") (name "unconnected-(U2-BP-Pad4)") (class "Default")
      (node (ref "U2") (pin "4") (pinfunction "BP_4") (pintype "passive"))
    )
    (net (code "59") (name "unconnected-(U4-ADC6-Pad19)") (class "Default")
      (node (ref "U4") (pin "19") (pinfunction "ADC6_19") (pintype "input+no_connect"))
    )
    (net (code "60") (name "unconnected-(U4-ADC7-Pad22)") (class "Default")
      (node (ref "U4") (pin "22") (pinfunction "ADC7_22") (pintype "input+no_connect"))
    )
  )
)
